# B5_EM_-X_SOLAR_PANEL.net
KiCad netlist of a schematic drawn in EAGLE
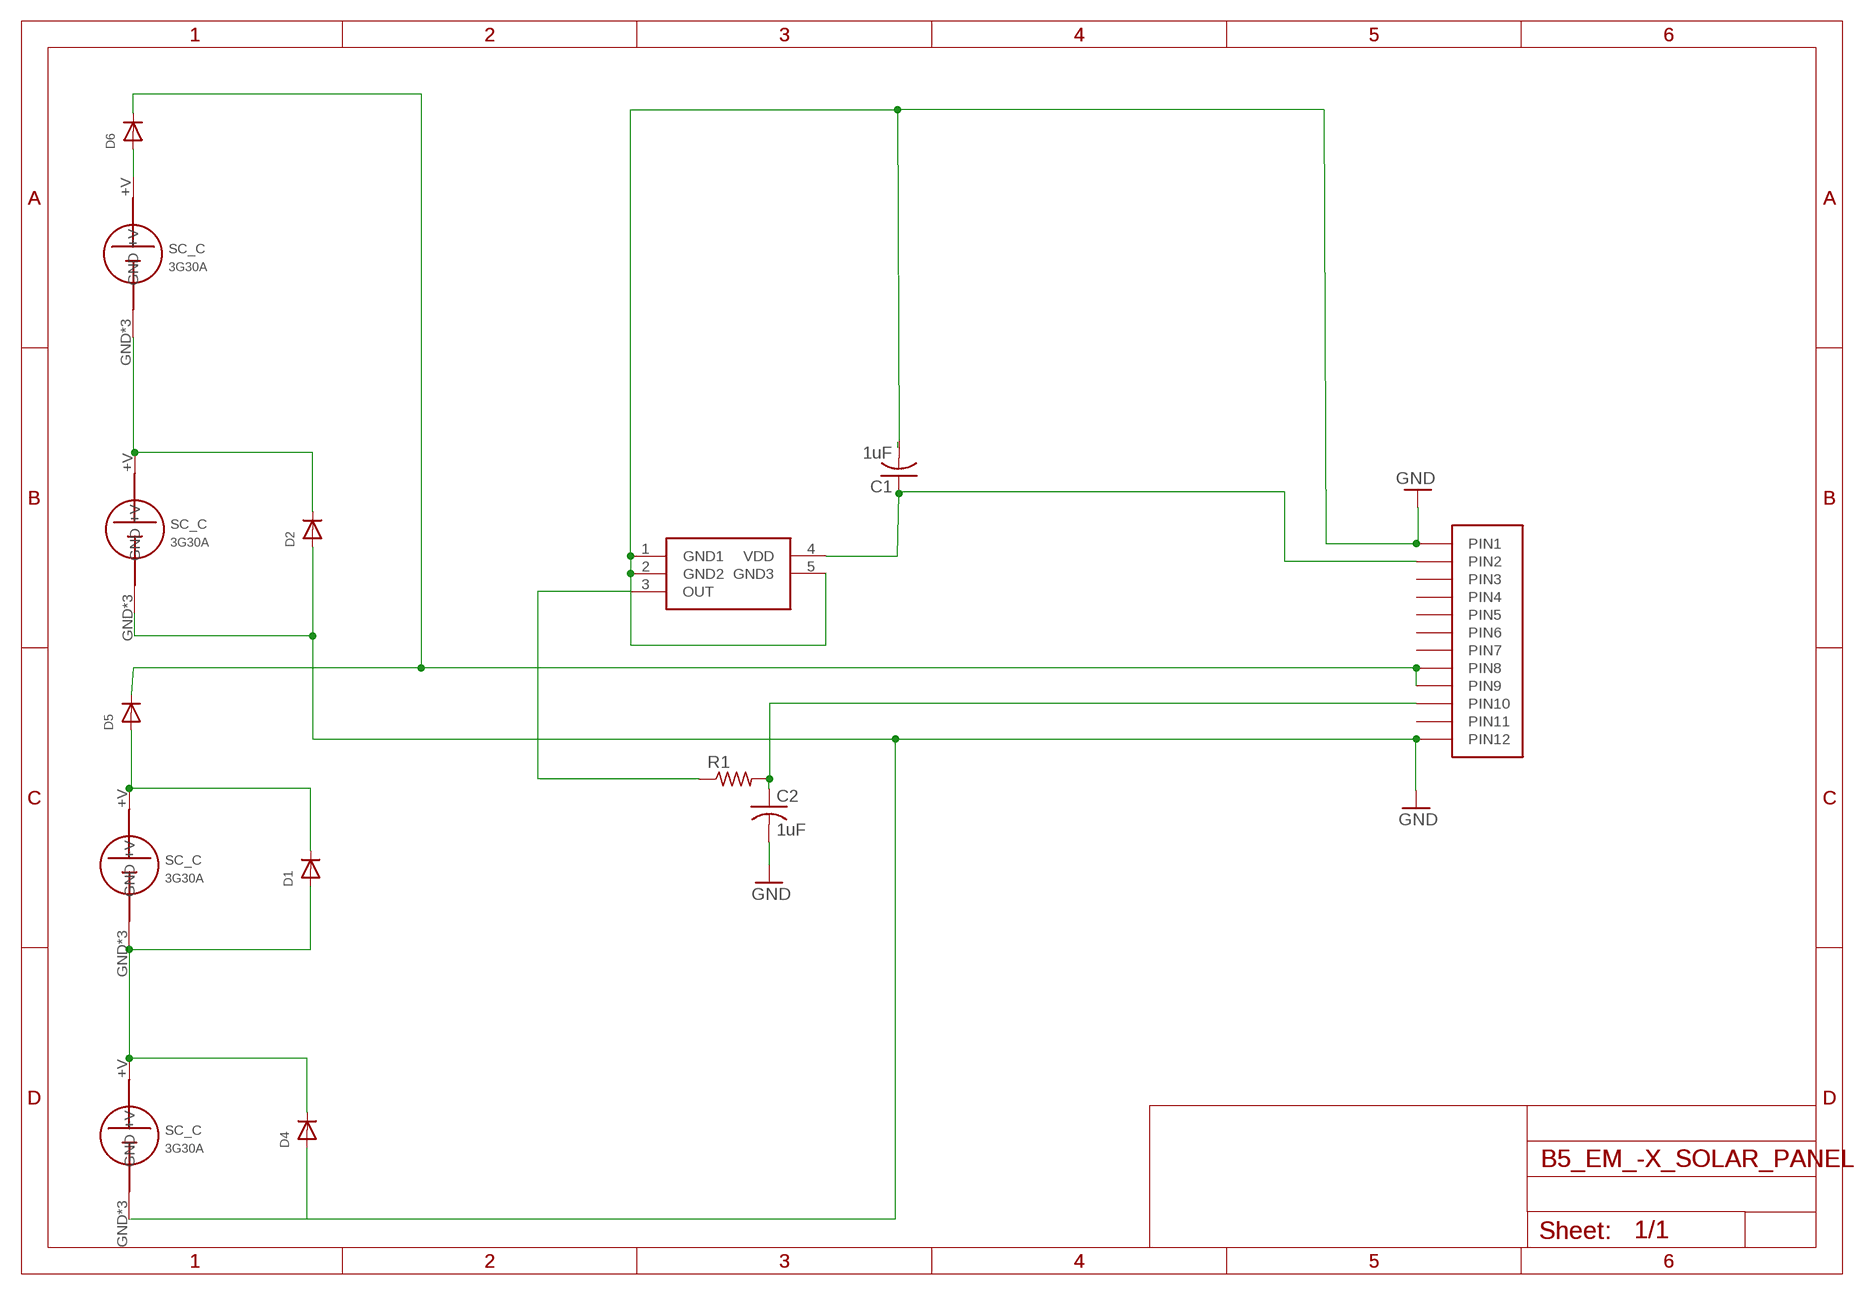
[diagram p0: schematic, sheet 1]

(export (version "E")
  (design (tool "Eeschema 10.0.6"))
  (components
    (comp (ref "C1")
      (value "1uF")
      (footprint "eagle-import:C0805")
      (libsource (lib "eagle-import") (part "C-USC0805"))
    )
    (comp (ref "C2")
      (value "1uF")
      (footprint "eagle-import:C0805")
      (libsource (lib "eagle-import") (part "C-USC0805"))
    )
    (comp (ref "D1")
      (value "DIODE_SOD-123FL")
      (footprint "eagle-import:SOD-123FL")
      (libsource (lib "eagle-import") (part "DIODE_SOD-123FL"))
    )
    (comp (ref "D2")
      (value "DIODE_SOD-123FL")
      (footprint "eagle-import:SOD-123FL")
      (libsource (lib "eagle-import") (part "DIODE_SOD-123FL"))
    )
    (comp (ref "D4")
      (value "DIODE_SOD-123FL")
      (footprint "eagle-import:SOD-123FL")
      (libsource (lib "eagle-import") (part "DIODE_SOD-123FL"))
    )
    (comp (ref "D5")
      (value "DIODE_SOD-123FL")
      (footprint "eagle-import:SOD-123FL")
      (libsource (lib "eagle-import") (part "DIODE_SOD-123FL"))
    )
    (comp (ref "D6")
      (value "DIODE_SOD-123FL")
      (footprint "eagle-import:SOD-123FL")
      (libsource (lib "eagle-import") (part "DIODE_SOD-123FL"))
    )
    (comp (ref "R1")
      (value "R-US_R0402")
      (footprint "eagle-import:R0402")
      (libsource (lib "eagle-import") (part "R-US_R0402"))
    )
    (comp (ref "U$1")
      (value "HEADER12PIN")
      (footprint "eagle-import:HEADER12PIN")
      (libsource (lib "eagle-import") (part "HEADER12PIN"))
    )
    (comp (ref "U$2")
      (value "SC_C")
      (footprint "eagle-import:SC_C")
      (libsource (lib "eagle-import") (part "SC_C"))
    )
    (comp (ref "U$3")
      (value "LMT84DCKT")
      (footprint "eagle-import:SOT65P210X110-5N")
      (fields (field (name "RS_PART_NUMBER") "8115860"))
      (libsource (lib "eagle-import") (part "LMT84DCKT"))
    )
    (comp (ref "U$4")
      (value "SC_C")
      (footprint "eagle-import:SC_C")
      (libsource (lib "eagle-import") (part "SC_C"))
    )
    (comp (ref "U$5")
      (value "SC_C")
      (footprint "eagle-import:SC_C")
      (libsource (lib "eagle-import") (part "SC_C"))
    )
    (comp (ref "U$6")
      (value "SC_C")
      (footprint "eagle-import:SC_C")
      (libsource (lib "eagle-import") (part "SC_C"))
    )
  )
  (nets
    (net (code "1") (name "GND") (class "Default")
      (node (ref "C1") (pin "2") (pinfunction "2_2") (pintype "passive"))
      (node (ref "C2") (pin "2") (pinfunction "2_2") (pintype "passive"))
      (node (ref "D2") (pin "A") (pinfunction "A_A") (pintype "passive"))
      (node (ref "D4") (pin "A") (pinfunction "A_A") (pintype "passive"))
      (node (ref "U$1") (pin "P1") (pinfunction "PIN1_P1") (pintype "bidirectional"))
      (node (ref "U$1") (pin "P12") (pinfunction "PIN12_P12") (pintype "bidirectional"))
      (node (ref "U$3") (pin "1") (pinfunction "GND1_1") (pintype "power_in"))
      (node (ref "U$3") (pin "2") (pinfunction "GND2_2") (pintype "power_in"))
      (node (ref "U$3") (pin "5") (pinfunction "GND3_5") (pintype "power_in"))
      (node (ref "U$4") (pin "GND") (pinfunction "GND_GND") (pintype "bidirectional"))
      (node (ref "U$4") (pin "GND1") (pinfunction "GND_GND1") (pintype "bidirectional"))
      (node (ref "U$4") (pin "GND2") (pinfunction "GND_GND2") (pintype "bidirectional"))
      (node (ref "U$6") (pin "GND") (pinfunction "GND_GND") (pintype "bidirectional"))
      (node (ref "U$6") (pin "GND1") (pinfunction "GND_GND1") (pintype "bidirectional"))
      (node (ref "U$6") (pin "GND2") (pinfunction "GND_GND2") (pintype "bidirectional"))
    )
    (net (code "2") (name "Net-(D1-PadA)") (class "Default")
      (node (ref "D1") (pin "A") (pinfunction "A_A") (pintype "passive"))
      (node (ref "D4") (pin "C") (pinfunction "C_C") (pintype "passive"))
      (node (ref "U$2") (pin "GND") (pinfunction "GND_GND") (pintype "bidirectional"))
      (node (ref "U$2") (pin "GND1") (pinfunction "GND_GND1") (pintype "bidirectional"))
      (node (ref "U$2") (pin "GND2") (pinfunction "GND_GND2") (pintype "bidirectional"))
      (node (ref "U$6") (pin "+V") (pinfunction "+V_+V") (pintype "bidirectional"))
    )
    (net (code "3") (name "Net-(D1-PadC)") (class "Default")
      (node (ref "D1") (pin "C") (pinfunction "C_C") (pintype "passive"))
      (node (ref "D5") (pin "A") (pinfunction "A_A") (pintype "passive"))
      (node (ref "U$2") (pin "+V") (pinfunction "+V_+V") (pintype "bidirectional"))
    )
    (net (code "4") (name "Net-(D2-PadC)") (class "Default")
      (node (ref "D2") (pin "C") (pinfunction "C_C") (pintype "passive"))
      (node (ref "U$4") (pin "+V") (pinfunction "+V_+V") (pintype "bidirectional"))
      (node (ref "U$5") (pin "GND") (pinfunction "GND_GND") (pintype "bidirectional"))
      (node (ref "U$5") (pin "GND1") (pinfunction "GND_GND1") (pintype "bidirectional"))
      (node (ref "U$5") (pin "GND2") (pinfunction "GND_GND2") (pintype "bidirectional"))
    )
    (net (code "5") (name "Net-(D6-PadA)") (class "Default")
      (node (ref "D6") (pin "A") (pinfunction "A_A") (pintype "passive"))
      (node (ref "U$5") (pin "+V") (pinfunction "+V_+V") (pintype "bidirectional"))
    )
    (net (code "6") (name "Net-(U$1-PIN2)") (class "Default")
      (node (ref "C1") (pin "1") (pinfunction "1_1") (pintype "passive"))
      (node (ref "U$1") (pin "P2") (pinfunction "PIN2_P2") (pintype "bidirectional"))
      (node (ref "U$3") (pin "4") (pinfunction "VDD_4") (pintype "power_in"))
    )
    (net (code "7") (name "Net-(U$1-PIN8)") (class "Default")
      (node (ref "D5") (pin "C") (pinfunction "C_C") (pintype "passive"))
      (node (ref "D6") (pin "C") (pinfunction "C_C") (pintype "passive"))
      (node (ref "U$1") (pin "P8") (pinfunction "PIN8_P8") (pintype "bidirectional"))
      (node (ref "U$1") (pin "P9") (pinfunction "PIN9_P9") (pintype "bidirectional"))
    )
    (net (code "8") (name "Net-(U$1-PIN10)") (class "Default")
      (node (ref "C2") (pin "1") (pinfunction "1_1") (pintype "passive"))
      (node (ref "R1") (pin "2") (pinfunction "2_2") (pintype "passive"))
      (node (ref "U$1") (pin "P10") (pinfunction "PIN10_P10") (pintype "bidirectional"))
    )
    (net (code "9") (name "Net-(U$3-OUT)") (class "Default")
      (node (ref "R1") (pin "1") (pinfunction "1_1") (pintype "passive"))
      (node (ref "U$3") (pin "3") (pinfunction "OUT_3") (pintype "output"))
    )
    (net (code "10") (name "unconnected-(U$1-PIN3-PadP3)") (class "Default")
      (node (ref "U$1") (pin "P3") (pinfunction "PIN3_P3") (pintype "bidirectional"))
    )
    (net (code "11") (name "unconnected-(U$1-PIN4-PadP4)") (class "Default")
      (node (ref "U$1") (pin "P4") (pinfunction "PIN4_P4") (pintype "bidirectional"))
    )
    (net (code "12") (name "unconnected-(U$1-PIN5-PadP5)") (class "Default")
      (node (ref "U$1") (pin "P5") (pinfunction "PIN5_P5") (pintype "bidirectional"))
    )
    (net (code "13") (name "unconnected-(U$1-PIN6-PadP6)") (class "Default")
      (node (ref "U$1") (pin "P6") (pinfunction "PIN6_P6") (pintype "bidirectional"))
    )
    (net (code "14") (name "unconnected-(U$1-PIN7-PadP7)") (class "Default")
      (node (ref "U$1") (pin "P7") (pinfunction "PIN7_P7") (pintype "bidirectional"))
    )
    (net (code "15") (name "unconnected-(U$1-PIN11-PadP11)") (class "Default")
      (node (ref "U$1") (pin "P11") (pinfunction "PIN11_P11") (pintype "bidirectional"))
    )
  )
)
